# 03_TF_CARD_SATA.net
KiCad netlist of a schematic drawn in Altium Designer
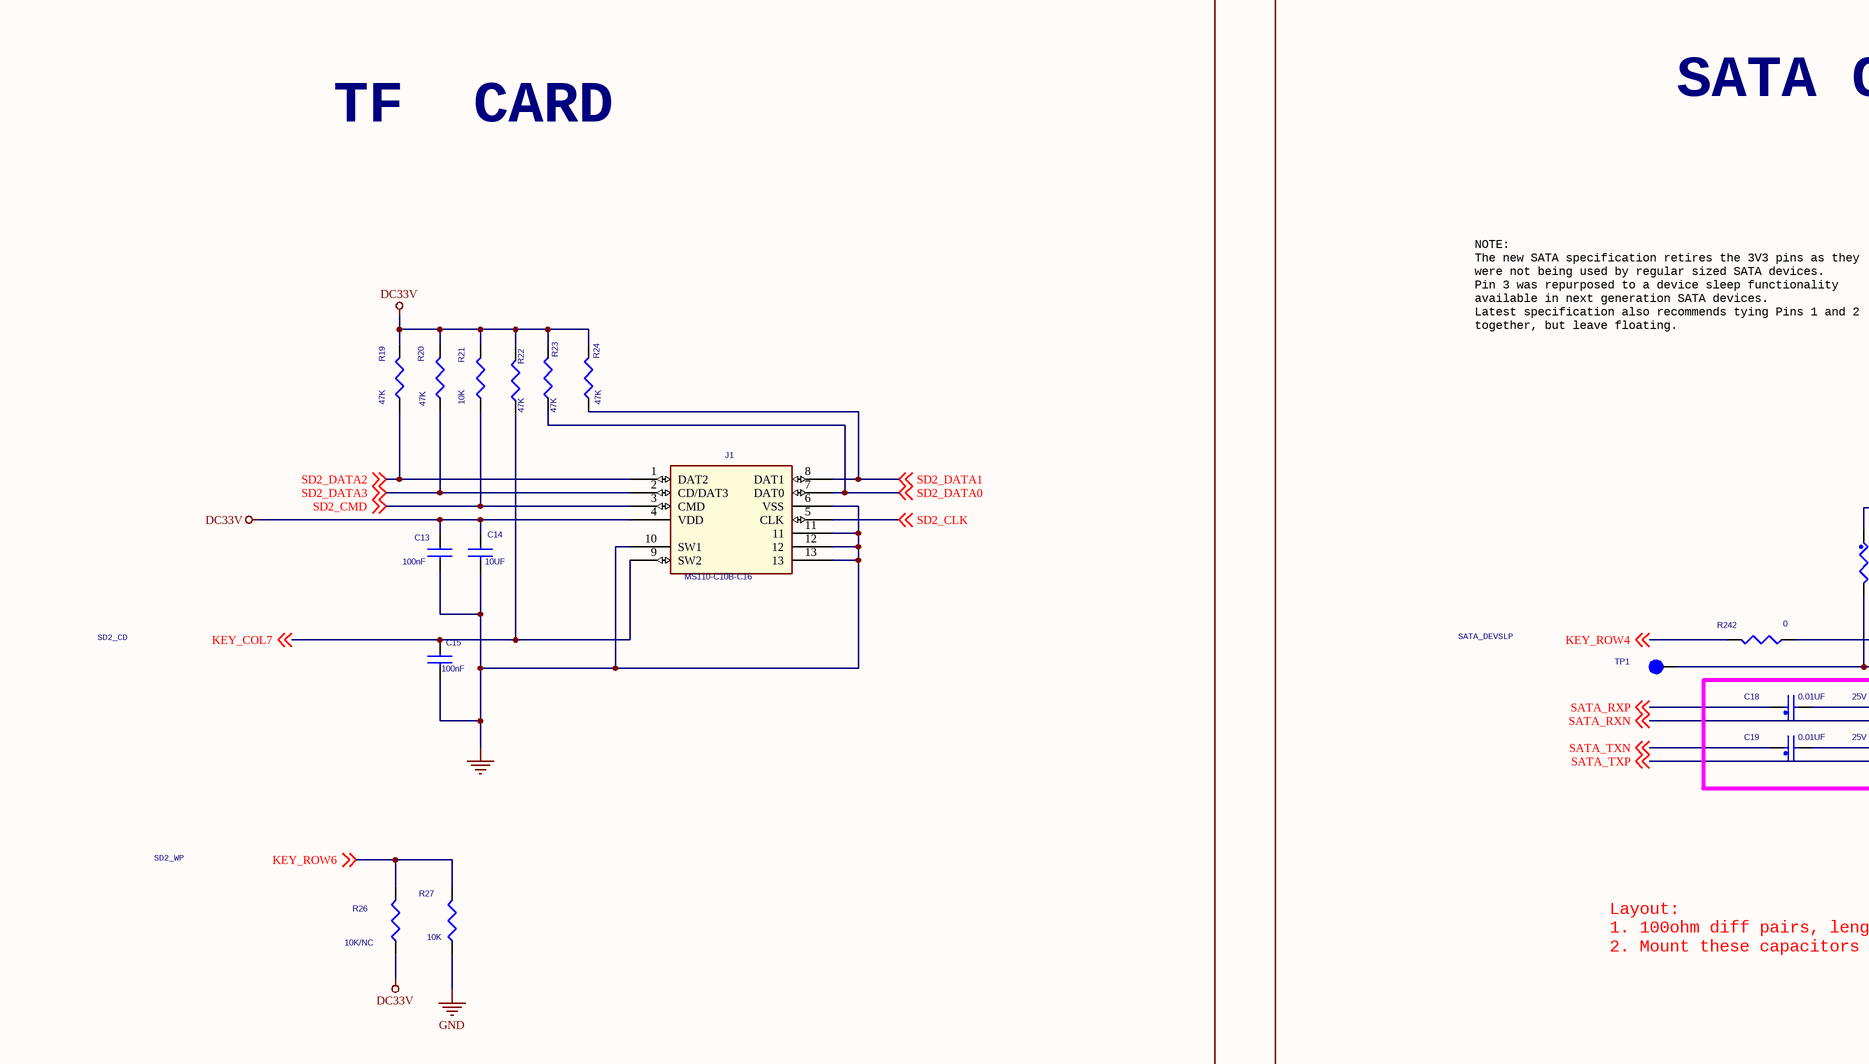
[diagram p0: 03 TF CARD, SATA.SchDoc, top left]
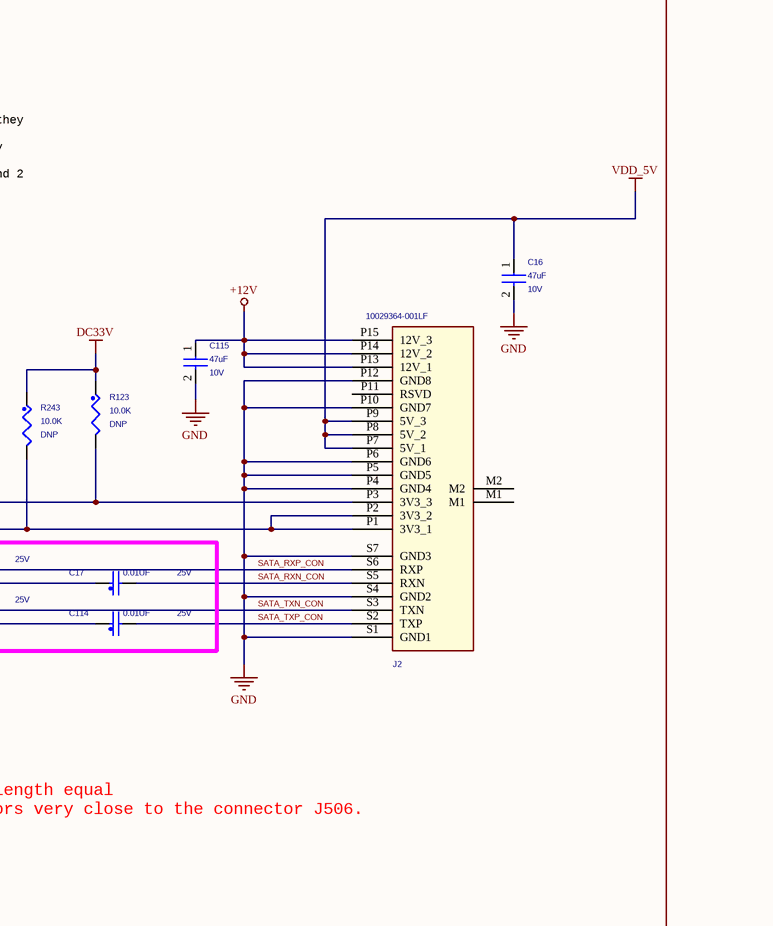
[diagram p1: 03 TF CARD, SATA.SchDoc, top right]
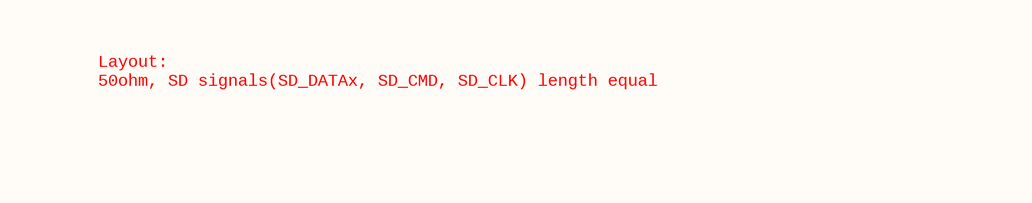
[diagram p2: 03 TF CARD, SATA.SchDoc, bottom left]
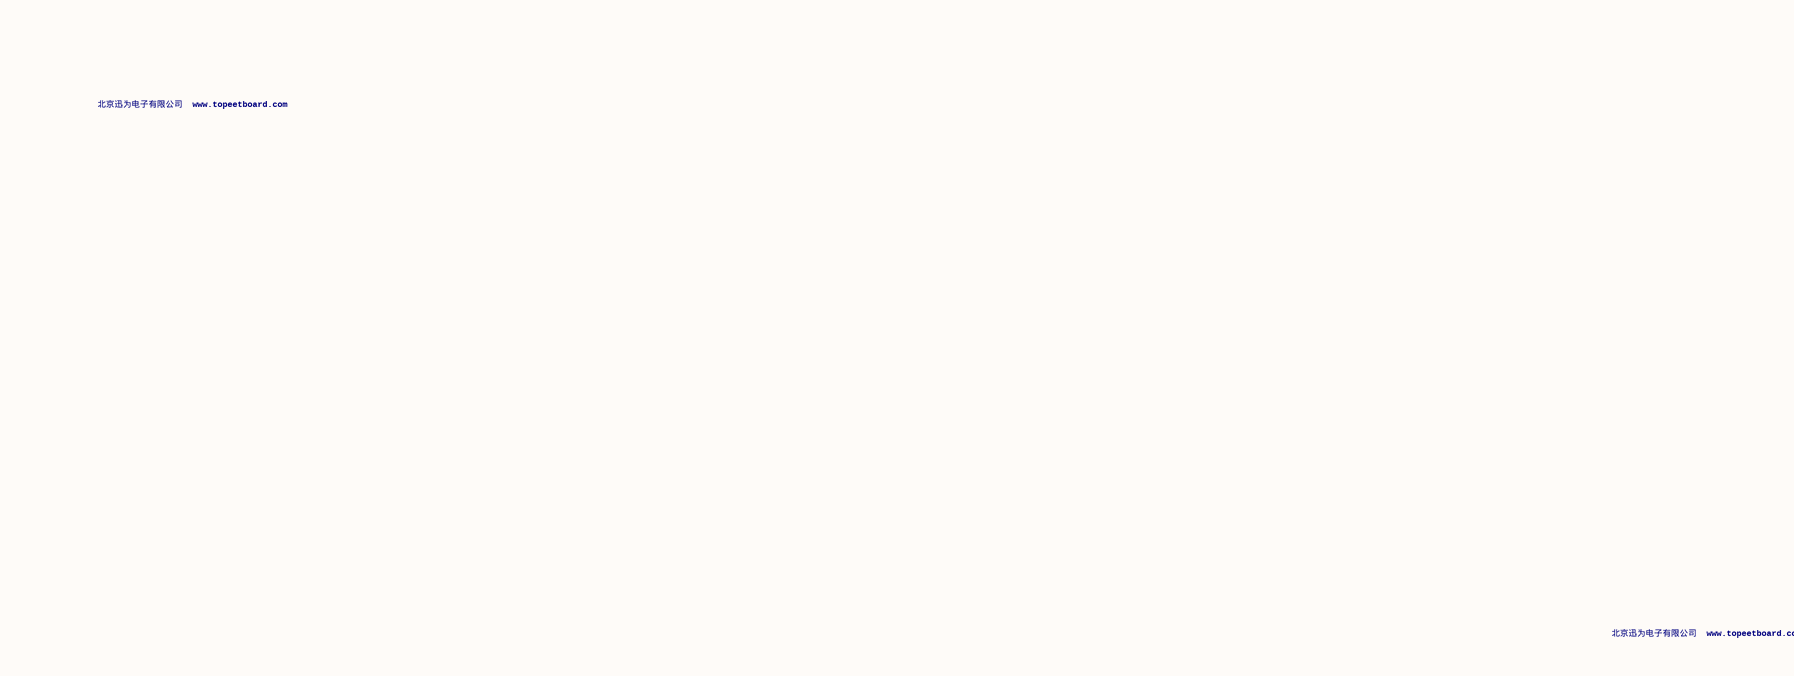
[diagram p3: 03 TF CARD, SATA.SchDoc, bottom right]

(export (version "E")
  (design (tool "Eeschema 10.0.6"))
  (components
    (comp (ref "C13") (value "100nF") (footprint "C0402") (libsource (lib "*") (part "C0402_0")))
    (comp (ref "C14") (value "10UF") (footprint "C0402") (libsource (lib "*") (part "C0402_0")))
    (comp (ref "C15") (value "100nF") (footprint "C0402") (libsource (lib "*") (part "C0402_0")))
    (comp (ref "C16")
      (value "47uF")
      (description "CAP CER 47uF 10V 20% X5R 1206")
      (fields (field (name "WVDC") "10V") (field (name "TOLERANCE") "20%") (field (name "VOLTAGE") "10V"))
      (libsource (lib "*") (part "MOT_CAP"))
    )
    (comp (ref "C17")
      (value "0.01UF")
      (description "CAP CER 0.01UF 6.3V 10% X7R 0201")
      (fields (field (name "VOLTAGE") "6.3V") (field (name "WVDC") "25V") (field (name "TOLERANCE") "10%"))
      (libsource (lib "*") (part "CAP_NP"))
    )
    (comp (ref "C18")
      (value "0.01UF")
      (description "CAP CER 0.01UF 6.3V 10% X7R 0201")
      (fields (field (name "VOLTAGE") "6.3V") (field (name "TOLERANCE") "10%") (field (name "WVDC") "25V"))
      (libsource (lib "*") (part "CAP_NP"))
    )
    (comp (ref "C19")
      (value "0.01UF")
      (description "CAP CER 0.01UF 6.3V 10% X7R 0201")
      (fields (field (name "VOLTAGE") "6.3V") (field (name "TOLERANCE") "10%") (field (name "WVDC") "25V"))
      (libsource (lib "*") (part "CAP_NP"))
    )
    (comp (ref "C114")
      (value "0.01UF")
      (description "CAP CER 0.01UF 6.3V 10% X7R 0201")
      (fields (field (name "VOLTAGE") "6.3V") (field (name "WVDC") "25V") (field (name "TOLERANCE") "10%"))
      (libsource (lib "*") (part "CAP_NP"))
    )
    (comp (ref "C115")
      (value "47uF")
      (description "CAP CER 47uF 10V 20% X5R 1206")
      (fields (field (name "VOLTAGE") "10V") (field (name "TOLERANCE") "20%") (field (name "WVDC") "10V"))
      (libsource (lib "*") (part "MOT_CAP"))
    )
    (comp (ref "J1") (value "MS110-C10B-C16") (libsource (lib "*") (part "MS110-C10B-C16_2")))
    (comp (ref "J2")
      (value "10029364-001LF")
      (description "CON 22 SATA SKT RA SMT 50MIL SP 221H AU")
      (libsource (lib "*") (part "CONN_SATA_22P"))
    )
    (comp (ref "R19") (value "47K") (footprint "R1005") (libsource (lib "*") (part "R1005_0_Dup2")))
    (comp (ref "R20") (value "47K") (footprint "R1005") (libsource (lib "*") (part "R1005_0_Dup2")))
    (comp (ref "R21") (value "10K") (footprint "R1005") (libsource (lib "*") (part "R1005_0_Dup2")))
    (comp (ref "R22") (value "47K") (footprint "R1005") (libsource (lib "*") (part "R1005_0_Dup2")))
    (comp (ref "R23") (value "47K") (footprint "R1005") (libsource (lib "*") (part "R1005_0_Dup2")))
    (comp (ref "R24") (value "47K") (footprint "R1005") (libsource (lib "*") (part "R1005_0_Dup2")))
    (comp (ref "R26") (value "10K/NC") (footprint "R1005") (libsource (lib "*") (part "R1005_0_Dup2")))
    (comp (ref "R27") (value "10K") (footprint "R1005") (libsource (lib "*") (part "R1005_0_Dup2")))
    (comp (ref "R123")
      (value "10.0K")
      (description "RES MF 10.0K 1/16W 1% AEC-Q200 0402")
      (fields (field (name "TOLERANCE") "1%") (field (name "ASSY_OPT") "DNP"))
      (libsource (lib "*") (part "RES_Dup1"))
    )
    (comp (ref "R242") (value "0") (libsource (lib "*") (part "R_Dup1")))
    (comp (ref "R243")
      (value "10.0K")
      (description "RES MF 10.0K 1/16W 1% AEC-Q200 0402")
      (fields (field (name "TOLERANCE") "1%") (field (name "ASSY_OPT") "DNP"))
      (libsource (lib "*") (part "RES_Dup1"))
    )
    (comp (ref "TP1")
      (value "tpad_020")
      (description "TEST POINT PAD 0.5MM DIA SMT, NO PART TO ORDER")
      (libsource (lib "*") (part "TESTLOOP"))
    )
  )
  (nets
    (net (code "1") (name "+12V") (class "Default")
      (node (ref "C115") (pin "1") (pinfunction "1_1") (pintype "passive"))
      (node (ref "J2") (pin "P13") (pinfunction "12V_1_P13") (pintype "power_in"))
      (node (ref "J2") (pin "P14") (pinfunction "12V_2_P14") (pintype "power_in"))
      (node (ref "J2") (pin "P15") (pinfunction "12V_3_P15") (pintype "power_in"))
    )
    (net (code "2") (name "/SATA_RXN_CON") (class "Default")
      (node (ref "C17") (pin "2") (pinfunction "2_2") (pintype "passive"))
      (node (ref "J2") (pin "S5") (pinfunction "RXN_S5") (pintype "passive"))
    )
    (net (code "3") (name "/SATA_RXP_CON") (class "Default")
      (node (ref "C18") (pin "2") (pinfunction "2_2") (pintype "passive"))
      (node (ref "J2") (pin "S6") (pinfunction "RXP_S6") (pintype "passive"))
    )
    (net (code "4") (name "/SATA_TXN_CON") (class "Default")
      (node (ref "C19") (pin "2") (pinfunction "2_2") (pintype "passive"))
      (node (ref "J2") (pin "S3") (pinfunction "TXN_S3") (pintype "passive"))
    )
    (net (code "5") (name "/SATA_TXP_CON") (class "Default")
      (node (ref "C114") (pin "2") (pinfunction "2_2") (pintype "passive"))
      (node (ref "J2") (pin "S2") (pinfunction "TXP_S2") (pintype "passive"))
    )
    (net (code "6") (name "DC33V") (class "Default")
      (node (ref "C13") (pin "1") (pinfunction "1_1") (pintype "passive"))
      (node (ref "C14") (pin "1") (pinfunction "1_1") (pintype "passive"))
      (node (ref "J1") (pin "4") (pinfunction "VDD_4") (pintype "power_in"))
      (node (ref "R123") (pin "1") (pinfunction "1_1") (pintype "passive"))
      (node (ref "R19") (pin "2") (pinfunction "2_2") (pintype "passive"))
      (node (ref "R20") (pin "2") (pinfunction "2_2") (pintype "passive"))
      (node (ref "R21") (pin "2") (pinfunction "2_2") (pintype "passive"))
      (node (ref "R22") (pin "2") (pinfunction "2_2") (pintype "passive"))
      (node (ref "R23") (pin "2") (pinfunction "2_2") (pintype "passive"))
      (node (ref "R24") (pin "2") (pinfunction "2_2") (pintype "passive"))
      (node (ref "R243") (pin "1") (pinfunction "1_1") (pintype "passive"))
      (node (ref "R26") (pin "1") (pinfunction "1_1") (pintype "passive"))
    )
    (net (code "7") (name "GND") (class "Default")
      (node (ref "C115") (pin "2") (pinfunction "2_2") (pintype "passive"))
      (node (ref "C13") (pin "2") (pinfunction "2_2") (pintype "passive"))
      (node (ref "C14") (pin "2") (pinfunction "2_2") (pintype "passive"))
      (node (ref "C15") (pin "2") (pinfunction "2_2") (pintype "passive"))
      (node (ref "C16") (pin "2") (pinfunction "2_2") (pintype "passive"))
      (node (ref "J1") (pin "10") (pinfunction "SW1_10") (pintype "power_in"))
      (node (ref "J1") (pin "11") (pinfunction "11_11") (pintype "passive"))
      (node (ref "J1") (pin "12") (pinfunction "12_12") (pintype "passive"))
      (node (ref "J1") (pin "13") (pinfunction "13_13") (pintype "passive"))
      (node (ref "J1") (pin "6") (pinfunction "VSS_6") (pintype "power_in"))
      (node (ref "J2") (pin "P10") (pinfunction "GND7_P10") (pintype "power_in"))
      (node (ref "J2") (pin "P12") (pinfunction "GND8_P12") (pintype "power_in"))
      (node (ref "J2") (pin "P4") (pinfunction "GND4_P4") (pintype "power_in"))
      (node (ref "J2") (pin "P5") (pinfunction "GND5_P5") (pintype "power_in"))
      (node (ref "J2") (pin "P6") (pinfunction "GND6_P6") (pintype "power_in"))
      (node (ref "J2") (pin "S1") (pinfunction "GND1_S1") (pintype "power_in"))
      (node (ref "J2") (pin "S4") (pinfunction "GND2_S4") (pintype "power_in"))
      (node (ref "J2") (pin "S7") (pinfunction "GND3_S7") (pintype "power_in"))
      (node (ref "R27") (pin "1") (pinfunction "1_1") (pintype "passive"))
    )
    (net (code "8") (name "KEY_COL7") (class "Default")
      (node (ref "C15") (pin "1") (pinfunction "1_1") (pintype "passive"))
      (node (ref "J1") (pin "9") (pinfunction "SW2_9") (pintype "bidirectional"))
      (node (ref "R22") (pin "1") (pinfunction "1_1") (pintype "passive"))
    )
    (net (code "9") (name "KEY_ROW4") (class "Default")
      (node (ref "R242") (pin "2") (pinfunction "2_2") (pintype "passive"))
    )
    (net (code "10") (name "KEY_ROW6") (class "Default")
      (node (ref "R26") (pin "2") (pinfunction "2_2") (pintype "passive"))
      (node (ref "R27") (pin "2") (pinfunction "2_2") (pintype "passive"))
    )
    (net (code "11") (name "Net-(J2-3V3_1)") (class "Default")
      (node (ref "J2") (pin "P1") (pinfunction "3V3_1_P1") (pintype "power_in"))
      (node (ref "J2") (pin "P2") (pinfunction "3V3_2_P2") (pintype "power_in"))
      (node (ref "R243") (pin "2") (pinfunction "2_2") (pintype "passive"))
      (node (ref "TP1") (pin "1") (pinfunction "Pin1_1") (pintype "passive"))
    )
    (net (code "12") (name "Net-(J2-3V3_3)") (class "Default")
      (node (ref "J2") (pin "P3") (pinfunction "3V3_3_P3") (pintype "power_in"))
      (node (ref "R123") (pin "2") (pinfunction "2_2") (pintype "passive"))
      (node (ref "R242") (pin "1") (pinfunction "1_1") (pintype "passive"))
    )
    (net (code "13") (name "SATA_RXN") (class "Default")
      (node (ref "C17") (pin "1") (pinfunction "1_1") (pintype "passive"))
    )
    (net (code "14") (name "SATA_RXP") (class "Default")
      (node (ref "C18") (pin "1") (pinfunction "1_1") (pintype "passive"))
    )
    (net (code "15") (name "SATA_TXN") (class "Default")
      (node (ref "C19") (pin "1") (pinfunction "1_1") (pintype "passive"))
    )
    (net (code "16") (name "SATA_TXP") (class "Default")
      (node (ref "C114") (pin "1") (pinfunction "1_1") (pintype "passive"))
    )
    (net (code "17") (name "SD2_CLK") (class "Default")
      (node (ref "J1") (pin "5") (pinfunction "CLK_5") (pintype "bidirectional"))
    )
    (net (code "18") (name "SD2_CMD") (class "Default")
      (node (ref "J1") (pin "3") (pinfunction "CMD_3") (pintype "bidirectional"))
      (node (ref "R21") (pin "1") (pinfunction "1_1") (pintype "passive"))
    )
    (net (code "19") (name "SD2_DATA0") (class "Default")
      (node (ref "J1") (pin "7") (pinfunction "DAT0_7") (pintype "bidirectional"))
      (node (ref "R23") (pin "1") (pinfunction "1_1") (pintype "passive"))
    )
    (net (code "20") (name "SD2_DATA1") (class "Default")
      (node (ref "J1") (pin "8") (pinfunction "DAT1_8") (pintype "bidirectional"))
      (node (ref "R24") (pin "1") (pinfunction "1_1") (pintype "passive"))
    )
    (net (code "21") (name "SD2_DATA2") (class "Default")
      (node (ref "J1") (pin "1") (pinfunction "DAT2_1") (pintype "bidirectional"))
      (node (ref "R19") (pin "1") (pinfunction "1_1") (pintype "passive"))
    )
    (net (code "22") (name "SD2_DATA3") (class "Default")
      (node (ref "J1") (pin "2") (pinfunction "CD/DAT3_2") (pintype "bidirectional"))
      (node (ref "R20") (pin "1") (pinfunction "1_1") (pintype "passive"))
    )
    (net (code "23") (name "VDD_5V") (class "Default")
      (node (ref "C16") (pin "1") (pinfunction "1_1") (pintype "passive"))
      (node (ref "J2") (pin "P7") (pinfunction "5V_1_P7") (pintype "power_in"))
      (node (ref "J2") (pin "P8") (pinfunction "5V_2_P8") (pintype "power_in"))
      (node (ref "J2") (pin "P9") (pinfunction "5V_3_P9") (pintype "power_in"))
    )
    (net (code "24") (name "unconnected-(J2-PadM1)") (class "Default")
      (node (ref "J2") (pin "M1") (pinfunction "M1_M1") (pintype "passive"))
    )
    (net (code "25") (name "unconnected-(J2-PadM2)") (class "Default")
      (node (ref "J2") (pin "M2") (pinfunction "M2_M2") (pintype "passive"))
    )
    (net (code "26") (name "unconnected-(J2-RSVD-PadP11)") (class "Default")
      (node (ref "J2") (pin "P11") (pinfunction "RSVD_P11") (pintype "power_in"))
    )
  )
)
